# Microcontroller.net
KiCad netlist of a schematic drawn in Altium Designer
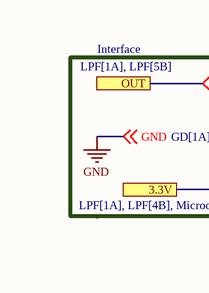
[diagram p0: Microcontroller.SchDoc, left]
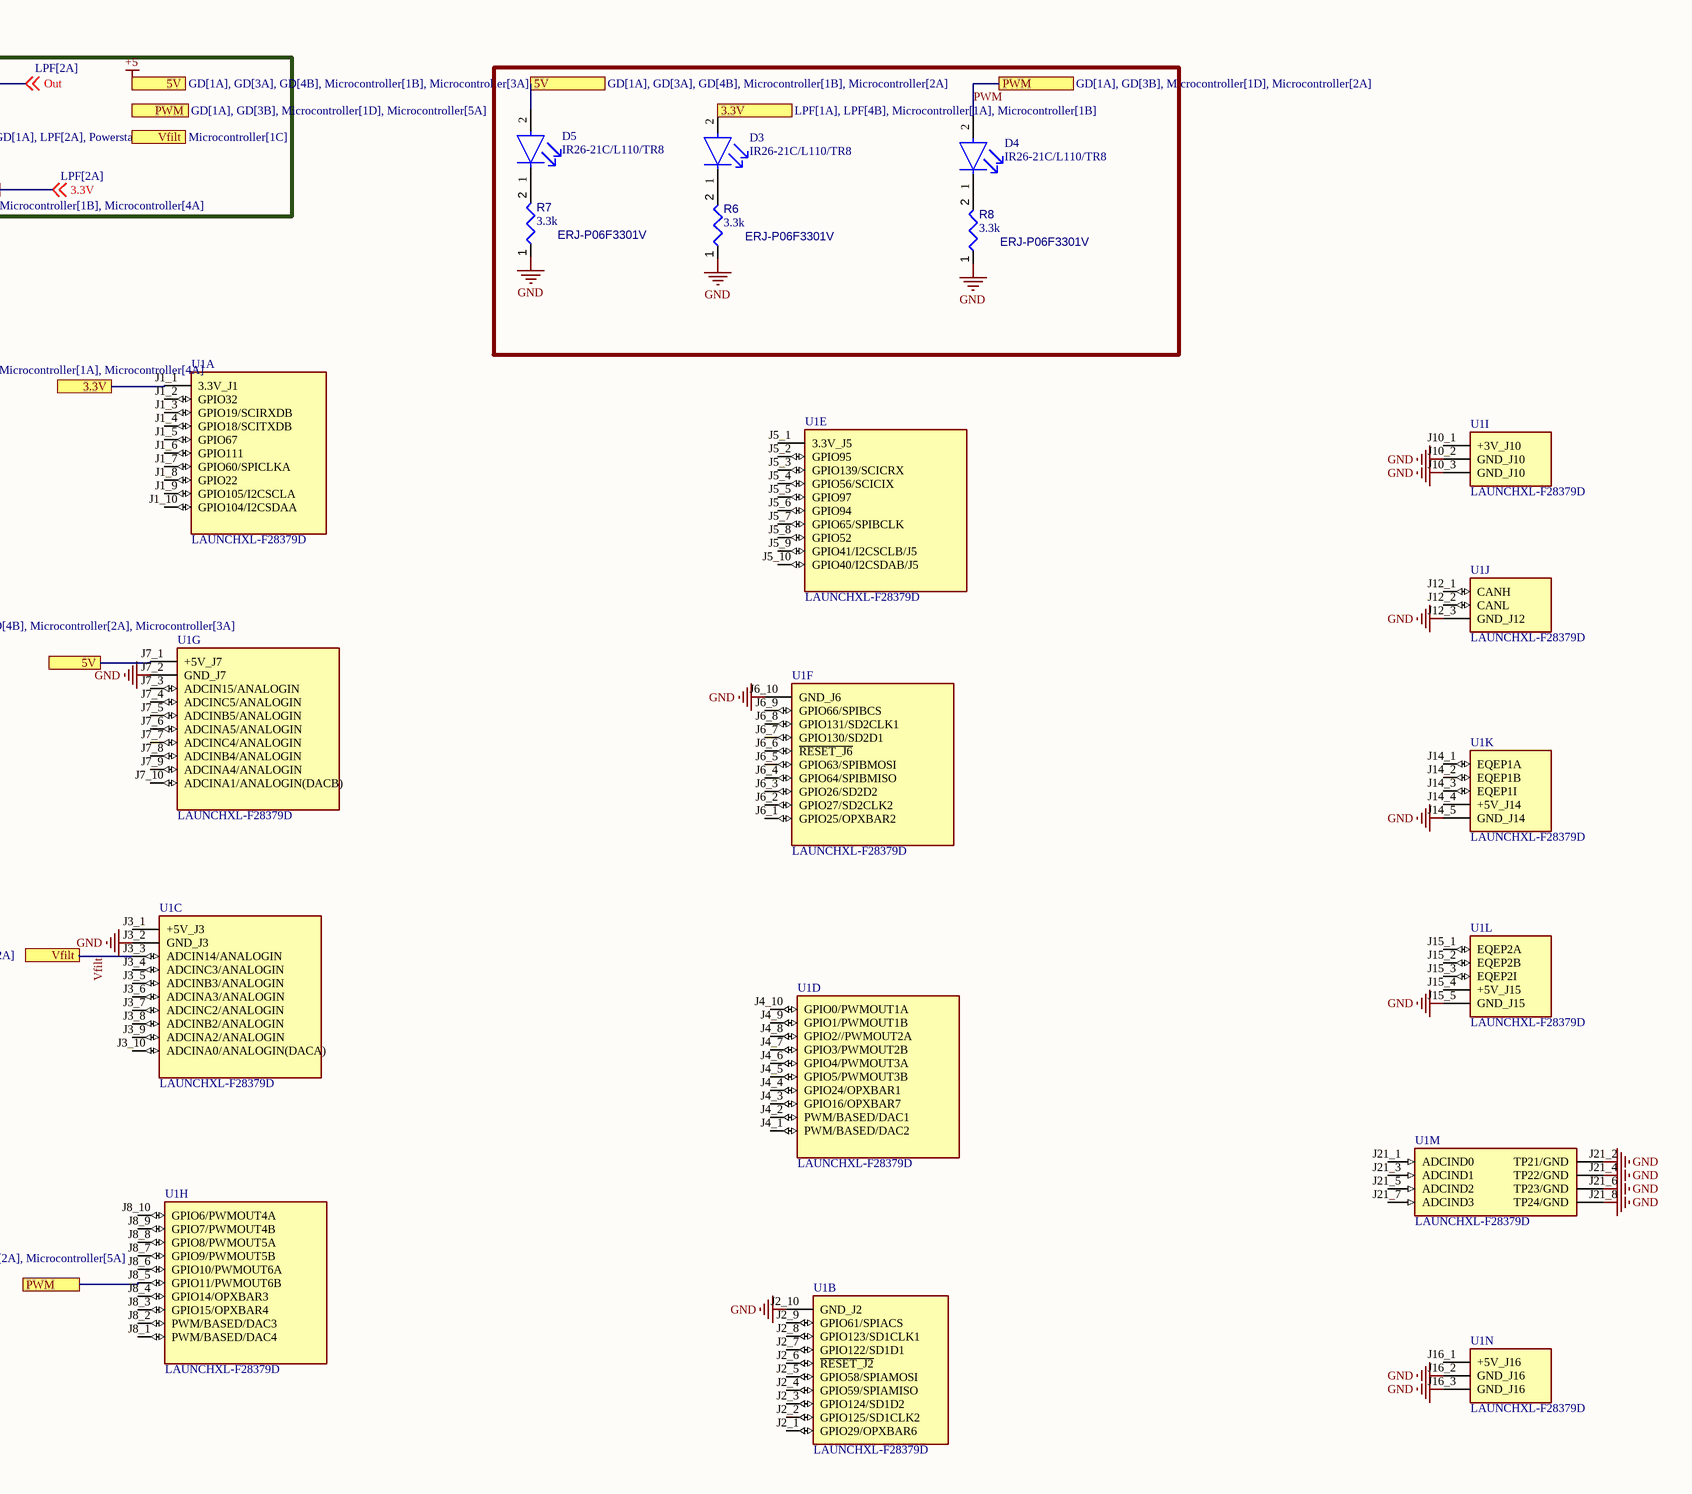
[diagram p1: Microcontroller.SchDoc, right]

(export (version "E")
  (design (tool "Eeschema 10.0.6"))
  (components
    (comp (ref "D3")
      (value "IR26-21C/L110/TR8")
      (footprint "FP-APTD3216CGCK-MFG")
      (description "LED GREEN CLEAR 2SMD")
      (libsource (lib "Altium Content Vault") (part "8706943c75ba83719d021d2fdc84c58"))
    )
    (comp (ref "D4")
      (value "IR26-21C/L110/TR8")
      (footprint "FP-APTD3216CGCK-MFG")
      (description "LED GREEN CLEAR 2SMD")
      (libsource (lib "Altium Content Vault") (part "8706943c75ba83719d021d2fdc84c58"))
    )
    (comp (ref "D5")
      (value "IR26-21C/L110/TR8")
      (footprint "FP-APTD3216CGCK-MFG")
      (description "LED GREEN CLEAR 2SMD")
      (libsource (lib "Altium Content Vault") (part "8706943c75ba83719d021d2fdc84c58"))
    )
    (comp (ref "R6")
      (value "ERJ-P06F3301V")
      (footprint "RESC0805(2012)_L")
      (description "1K 0.125W 5% 0805 (2012 Metric)  SMD")
      (fields
        (field (name "POWER") "125mW")
        (field (name "TOLERANCE") "5%")
        (field (name "ALTIUM_VALUE") "3.3k")
      )
      (libsource (lib "UWindsor Formula Electric") (part "1KR5J"))
    )
    (comp (ref "R7")
      (value "ERJ-P06F3301V")
      (footprint "RESC0805(2012)_L")
      (description "1K 0.125W 5% 0805 (2012 Metric)  SMD")
      (fields
        (field (name "POWER") "125mW")
        (field (name "TOLERANCE") "5%")
        (field (name "ALTIUM_VALUE") "3.3k")
      )
      (libsource (lib "UWindsor Formula Electric") (part "1KR5J"))
    )
    (comp (ref "R8")
      (value "ERJ-P06F3301V")
      (footprint "RESC0805(2012)_L")
      (description "1K 0.125W 5% 0805 (2012 Metric)  SMD")
      (fields
        (field (name "POWER") "125mW")
        (field (name "TOLERANCE") "5%")
        (field (name "ALTIUM_VALUE") "3.3k")
      )
      (libsource (lib "UWindsor Formula Electric") (part "1KR5J"))
    )
    (comp (ref "U1")
      (value "LAUNCHXL-F28379D")
      (footprint "MOD_LAUNCHXL-F28379D")
      (description "C2000 Delfino MCU F28379D LaunchPadâ„¢ development kit WITH 3D BODY")
      (fields (field (name "MF") "Texas Instruments"))
      (libsource (lib "UWindsor Formula Electric") (part "LAUNCHXL-F28379D"))
    )
  )
  (nets
    (net (code "1") (name "+5") (class "Default")
      (node (ref "D5") (pin "2") (pinfunction "A_2") (pintype "passive"))
      (node (ref "U1") (pin "J7_1") (pinfunction "+5V_J7_J7_1") (pintype "power_in"))
    )
    (net (code "2") (name "/PWM") (class "Default")
      (node (ref "D4") (pin "2") (pinfunction "A_2") (pintype "passive"))
      (node (ref "U1") (pin "J8_5") (pinfunction "GPIO11/PWMOUT6B_J8_5") (pintype "bidirectional"))
    )
    (net (code "3") (name "/Vfilt") (class "Default")
      (node (ref "U1") (pin "J3_3") (pinfunction "ADCIN14/ANALOGIN_J3_3") (pintype "bidirectional"))
    )
    (net (code "4") (name "3.3V") (class "Default")
      (node (ref "D3") (pin "2") (pinfunction "A_2") (pintype "passive"))
      (node (ref "U1") (pin "J1_1") (pinfunction "3.3V_J1_J1_1") (pintype "power_in"))
    )
    (net (code "5") (name "GND") (class "Default")
      (node (ref "R6") (pin "1") (pinfunction "1_1") (pintype "passive"))
      (node (ref "R7") (pin "1") (pinfunction "1_1") (pintype "passive"))
      (node (ref "R8") (pin "1") (pinfunction "1_1") (pintype "passive"))
      (node (ref "U1") (pin "J10_2") (pinfunction "GND_J10_J10_2") (pintype "power_in"))
      (node (ref "U1") (pin "J10_3") (pinfunction "GND_J10_J10_3") (pintype "power_in"))
      (node (ref "U1") (pin "J12_3") (pinfunction "GND_J12_J12_3") (pintype "power_in"))
      (node (ref "U1") (pin "J14_5") (pinfunction "GND_J14_J14_5") (pintype "power_in"))
      (node (ref "U1") (pin "J15_5") (pinfunction "GND_J15_J15_5") (pintype "power_in"))
      (node (ref "U1") (pin "J16_2") (pinfunction "GND_J16_J16_2") (pintype "power_in"))
      (node (ref "U1") (pin "J16_3") (pinfunction "GND_J16_J16_3") (pintype "power_in"))
      (node (ref "U1") (pin "J21_2") (pinfunction "TP21/GND_J21_2") (pintype "power_in"))
      (node (ref "U1") (pin "J21_4") (pinfunction "TP22/GND_J21_4") (pintype "power_in"))
      (node (ref "U1") (pin "J21_6") (pinfunction "TP23/GND_J21_6") (pintype "power_in"))
      (node (ref "U1") (pin "J21_8") (pinfunction "TP24/GND_J21_8") (pintype "power_in"))
      (node (ref "U1") (pin "J2_10") (pinfunction "GND_J2_J2_10") (pintype "power_in"))
      (node (ref "U1") (pin "J3_2") (pinfunction "GND_J3_J3_2") (pintype "power_in"))
      (node (ref "U1") (pin "J6_10") (pinfunction "GND_J6_J6_10") (pintype "power_in"))
      (node (ref "U1") (pin "J7_2") (pinfunction "GND_J7_J7_2") (pintype "power_in"))
    )
    (net (code "6") (name "Net-(D3-C)") (class "Default")
      (node (ref "D3") (pin "1") (pinfunction "C_1") (pintype "passive"))
      (node (ref "R6") (pin "2") (pinfunction "2_2") (pintype "passive"))
    )
    (net (code "7") (name "Net-(D4-C)") (class "Default")
      (node (ref "D4") (pin "1") (pinfunction "C_1") (pintype "passive"))
      (node (ref "R8") (pin "2") (pinfunction "2_2") (pintype "passive"))
    )
    (net (code "8") (name "Net-(D5-C)") (class "Default")
      (node (ref "D5") (pin "1") (pinfunction "C_1") (pintype "passive"))
      (node (ref "R7") (pin "2") (pinfunction "2_2") (pintype "passive"))
    )
    (net (code "10") (name "unconnected-(U1A-GPIO18{slash}SCITXDB-PadJ1_4)") (class "Default")
      (node (ref "U1") (pin "J1_4") (pinfunction "GPIO18/SCITXDB_J1_4") (pintype "bidirectional"))
    )
    (net (code "11") (name "unconnected-(U1A-GPIO19{slash}SCIRXDB-PadJ1_3)") (class "Default")
      (node (ref "U1") (pin "J1_3") (pinfunction "GPIO19/SCIRXDB_J1_3") (pintype "bidirectional"))
    )
    (net (code "12") (name "unconnected-(U1A-GPIO22-PadJ1_8)") (class "Default")
      (node (ref "U1") (pin "J1_8") (pinfunction "GPIO22_J1_8") (pintype "bidirectional"))
    )
    (net (code "13") (name "unconnected-(U1A-GPIO32-PadJ1_2)") (class "Default")
      (node (ref "U1") (pin "J1_2") (pinfunction "GPIO32_J1_2") (pintype "bidirectional"))
    )
    (net (code "14") (name "unconnected-(U1A-GPIO60{slash}SPICLKA-PadJ1_7)") (class "Default")
      (node (ref "U1") (pin "J1_7") (pinfunction "GPIO60/SPICLKA_J1_7") (pintype "bidirectional"))
    )
    (net (code "15") (name "unconnected-(U1A-GPIO67-PadJ1_5)") (class "Default")
      (node (ref "U1") (pin "J1_5") (pinfunction "GPIO67_J1_5") (pintype "bidirectional"))
    )
    (net (code "16") (name "unconnected-(U1A-GPIO104{slash}I2CSDAA-PadJ1_10)") (class "Default")
      (node (ref "U1") (pin "J1_10") (pinfunction "GPIO104/I2CSDAA_J1_10") (pintype "bidirectional"))
    )
    (net (code "17") (name "unconnected-(U1A-GPIO105{slash}I2CSCLA-PadJ1_9)") (class "Default")
      (node (ref "U1") (pin "J1_9") (pinfunction "GPIO105/I2CSCLA_J1_9") (pintype "bidirectional"))
    )
    (net (code "18") (name "unconnected-(U1A-GPIO111-PadJ1_6)") (class "Default")
      (node (ref "U1") (pin "J1_6") (pinfunction "GPIO111_J1_6") (pintype "bidirectional"))
    )
    (net (code "19") (name "unconnected-(U1B-GPIO29{slash}OPXBAR6-PadJ2_1)") (class "Default")
      (node (ref "U1") (pin "J2_1") (pinfunction "GPIO29/OPXBAR6_J2_1") (pintype "bidirectional"))
    )
    (net (code "20") (name "unconnected-(U1B-GPIO58{slash}SPIAMOSI-PadJ2_5)") (class "Default")
      (node (ref "U1") (pin "J2_5") (pinfunction "GPIO58/SPIAMOSI_J2_5") (pintype "bidirectional"))
    )
    (net (code "21") (name "unconnected-(U1B-GPIO59{slash}SPIAMISO-PadJ2_4)") (class "Default")
      (node (ref "U1") (pin "J2_4") (pinfunction "GPIO59/SPIAMISO_J2_4") (pintype "bidirectional"))
    )
    (net (code "22") (name "unconnected-(U1B-GPIO61{slash}SPIACS-PadJ2_9)") (class "Default")
      (node (ref "U1") (pin "J2_9") (pinfunction "GPIO61/SPIACS_J2_9") (pintype "bidirectional"))
    )
    (net (code "23") (name "unconnected-(U1B-GPIO122{slash}SD1D1-PadJ2_7)") (class "Default")
      (node (ref "U1") (pin "J2_7") (pinfunction "GPIO122/SD1D1_J2_7") (pintype "bidirectional"))
    )
    (net (code "24") (name "unconnected-(U1B-GPIO123{slash}SD1CLK1-PadJ2_8)") (class "Default")
      (node (ref "U1") (pin "J2_8") (pinfunction "GPIO123/SD1CLK1_J2_8") (pintype "bidirectional"))
    )
    (net (code "25") (name "unconnected-(U1B-GPIO124{slash}SD1D2-PadJ2_3)") (class "Default")
      (node (ref "U1") (pin "J2_3") (pinfunction "GPIO124/SD1D2_J2_3") (pintype "bidirectional"))
    )
    (net (code "26") (name "unconnected-(U1B-GPIO125{slash}SD1CLK2-PadJ2_2)") (class "Default")
      (node (ref "U1") (pin "J2_2") (pinfunction "GPIO125/SD1CLK2_J2_2") (pintype "bidirectional"))
    )
    (net (code "27") (name "unconnected-(U1B-~{RESET_J2}-PadJ2_6)") (class "Default")
      (node (ref "U1") (pin "J2_6") (pinfunction "~{RESET_J2}_J2_6") (pintype "bidirectional"))
    )
    (net (code "28") (name "unconnected-(U1C-+5V_J3-PadJ3_1)") (class "Default")
      (node (ref "U1") (pin "J3_1") (pinfunction "+5V_J3_J3_1") (pintype "power_in"))
    )
    (net (code "29") (name "unconnected-(U1C-ADCINA0{slash}ANALOGIN(DACA)-PadJ3_10)") (class "Default")
      (node (ref "U1") (pin "J3_10") (pinfunction "ADCINA0/ANALOGIN(DACA)_J3_10") (pintype "bidirectional"))
    )
    (net (code "30") (name "unconnected-(U1C-ADCINA2{slash}ANALOGIN-PadJ3_9)") (class "Default")
      (node (ref "U1") (pin "J3_9") (pinfunction "ADCINA2/ANALOGIN_J3_9") (pintype "bidirectional"))
    )
    (net (code "31") (name "unconnected-(U1C-ADCINA3{slash}ANALOGIN-PadJ3_6)") (class "Default")
      (node (ref "U1") (pin "J3_6") (pinfunction "ADCINA3/ANALOGIN_J3_6") (pintype "bidirectional"))
    )
    (net (code "32") (name "unconnected-(U1C-ADCINB2{slash}ANALOGIN-PadJ3_8)") (class "Default")
      (node (ref "U1") (pin "J3_8") (pinfunction "ADCINB2/ANALOGIN_J3_8") (pintype "bidirectional"))
    )
    (net (code "33") (name "unconnected-(U1C-ADCINB3{slash}ANALOGIN-PadJ3_5)") (class "Default")
      (node (ref "U1") (pin "J3_5") (pinfunction "ADCINB3/ANALOGIN_J3_5") (pintype "bidirectional"))
    )
    (net (code "34") (name "unconnected-(U1C-ADCINC2{slash}ANALOGIN-PadJ3_7)") (class "Default")
      (node (ref "U1") (pin "J3_7") (pinfunction "ADCINC2/ANALOGIN_J3_7") (pintype "bidirectional"))
    )
    (net (code "35") (name "unconnected-(U1C-ADCINC3{slash}ANALOGIN-PadJ3_4)") (class "Default")
      (node (ref "U1") (pin "J3_4") (pinfunction "ADCINC3/ANALOGIN_J3_4") (pintype "bidirectional"))
    )
    (net (code "36") (name "unconnected-(U1D-GPIO0{slash}PWMOUT1A-PadJ4_10)") (class "Default")
      (node (ref "U1") (pin "J4_10") (pinfunction "GPIO0/PWMOUT1A_J4_10") (pintype "bidirectional"))
    )
    (net (code "37") (name "unconnected-(U1D-GPIO1{slash}PWMOUT1B-PadJ4_9)") (class "Default")
      (node (ref "U1") (pin "J4_9") (pinfunction "GPIO1/PWMOUT1B_J4_9") (pintype "bidirectional"))
    )
    (net (code "38") (name "unconnected-(U1D-GPIO2{slash}{slash}PWMOUT2A-PadJ4_8)") (class "Default")
      (node (ref "U1") (pin "J4_8") (pinfunction "GPIO2//PWMOUT2A_J4_8") (pintype "bidirectional"))
    )
    (net (code "39") (name "unconnected-(U1D-GPIO3{slash}PWMOUT2B-PadJ4_7)") (class "Default")
      (node (ref "U1") (pin "J4_7") (pinfunction "GPIO3/PWMOUT2B_J4_7") (pintype "bidirectional"))
    )
    (net (code "40") (name "unconnected-(U1D-GPIO4{slash}PWMOUT3A-PadJ4_6)") (class "Default")
      (node (ref "U1") (pin "J4_6") (pinfunction "GPIO4/PWMOUT3A_J4_6") (pintype "bidirectional"))
    )
    (net (code "41") (name "unconnected-(U1D-GPIO5{slash}PWMOUT3B-PadJ4_5)") (class "Default")
      (node (ref "U1") (pin "J4_5") (pinfunction "GPIO5/PWMOUT3B_J4_5") (pintype "bidirectional"))
    )
    (net (code "42") (name "unconnected-(U1D-GPIO16{slash}OPXBAR7-PadJ4_3)") (class "Default")
      (node (ref "U1") (pin "J4_3") (pinfunction "GPIO16/OPXBAR7_J4_3") (pintype "bidirectional"))
    )
    (net (code "43") (name "unconnected-(U1D-GPIO24{slash}OPXBAR1-PadJ4_4)") (class "Default")
      (node (ref "U1") (pin "J4_4") (pinfunction "GPIO24/OPXBAR1_J4_4") (pintype "bidirectional"))
    )
    (net (code "44") (name "unconnected-(U1D-PWM{slash}BASED{slash}DAC1-PadJ4_2)") (class "Default")
      (node (ref "U1") (pin "J4_2") (pinfunction "PWM/BASED/DAC1_J4_2") (pintype "bidirectional"))
    )
    (net (code "45") (name "unconnected-(U1D-PWM{slash}BASED{slash}DAC2-PadJ4_1)") (class "Default")
      (node (ref "U1") (pin "J4_1") (pinfunction "PWM/BASED/DAC2_J4_1") (pintype "bidirectional"))
    )
    (net (code "46") (name "unconnected-(U1E-3.3V_J5-PadJ5_1)") (class "Default")
      (node (ref "U1") (pin "J5_1") (pinfunction "3.3V_J5_J5_1") (pintype "power_in"))
    )
    (net (code "47") (name "unconnected-(U1E-GPIO40{slash}I2CSDAB{slash}J5-PadJ5_10)") (class "Default")
      (node (ref "U1") (pin "J5_10") (pinfunction "GPIO40/I2CSDAB/J5_J5_10") (pintype "bidirectional"))
    )
    (net (code "48") (name "unconnected-(U1E-GPIO41{slash}I2CSCLB{slash}J5-PadJ5_9)") (class "Default")
      (node (ref "U1") (pin "J5_9") (pinfunction "GPIO41/I2CSCLB/J5_J5_9") (pintype "bidirectional"))
    )
    (net (code "49") (name "unconnected-(U1E-GPIO52-PadJ5_8)") (class "Default")
      (node (ref "U1") (pin "J5_8") (pinfunction "GPIO52_J5_8") (pintype "bidirectional"))
    )
    (net (code "50") (name "unconnected-(U1E-GPIO56{slash}SCICIX-PadJ5_4)") (class "Default")
      (node (ref "U1") (pin "J5_4") (pinfunction "GPIO56/SCICIX_J5_4") (pintype "bidirectional"))
    )
    (net (code "51") (name "unconnected-(U1E-GPIO65{slash}SPIBCLK-PadJ5_7)") (class "Default")
      (node (ref "U1") (pin "J5_7") (pinfunction "GPIO65/SPIBCLK_J5_7") (pintype "bidirectional"))
    )
    (net (code "52") (name "unconnected-(U1E-GPIO94-PadJ5_6)") (class "Default")
      (node (ref "U1") (pin "J5_6") (pinfunction "GPIO94_J5_6") (pintype "bidirectional"))
    )
    (net (code "53") (name "unconnected-(U1E-GPIO95-PadJ5_2)") (class "Default")
      (node (ref "U1") (pin "J5_2") (pinfunction "GPIO95_J5_2") (pintype "bidirectional"))
    )
    (net (code "54") (name "unconnected-(U1E-GPIO97-PadJ5_5)") (class "Default")
      (node (ref "U1") (pin "J5_5") (pinfunction "GPIO97_J5_5") (pintype "bidirectional"))
    )
    (net (code "55") (name "unconnected-(U1E-GPIO139{slash}SCICRX-PadJ5_3)") (class "Default")
      (node (ref "U1") (pin "J5_3") (pinfunction "GPIO139/SCICRX_J5_3") (pintype "bidirectional"))
    )
    (net (code "56") (name "unconnected-(U1F-GPIO25{slash}OPXBAR2-PadJ6_1)") (class "Default")
      (node (ref "U1") (pin "J6_1") (pinfunction "GPIO25/OPXBAR2_J6_1") (pintype "bidirectional"))
    )
    (net (code "57") (name "unconnected-(U1F-GPIO26{slash}SD2D2-PadJ6_3)") (class "Default")
      (node (ref "U1") (pin "J6_3") (pinfunction "GPIO26/SD2D2_J6_3") (pintype "bidirectional"))
    )
    (net (code "58") (name "unconnected-(U1F-GPIO27{slash}SD2CLK2-PadJ6_2)") (class "Default")
      (node (ref "U1") (pin "J6_2") (pinfunction "GPIO27/SD2CLK2_J6_2") (pintype "bidirectional"))
    )
    (net (code "59") (name "unconnected-(U1F-GPIO63{slash}SPIBMOSI-PadJ6_5)") (class "Default")
      (node (ref "U1") (pin "J6_5") (pinfunction "GPIO63/SPIBMOSI_J6_5") (pintype "bidirectional"))
    )
    (net (code "60") (name "unconnected-(U1F-GPIO64{slash}SPIBMISO-PadJ6_4)") (class "Default")
      (node (ref "U1") (pin "J6_4") (pinfunction "GPIO64/SPIBMISO_J6_4") (pintype "bidirectional"))
    )
    (net (code "61") (name "unconnected-(U1F-GPIO66{slash}SPIBCS-PadJ6_9)") (class "Default")
      (node (ref "U1") (pin "J6_9") (pinfunction "GPIO66/SPIBCS_J6_9") (pintype "bidirectional"))
    )
    (net (code "62") (name "unconnected-(U1F-GPIO130{slash}SD2D1-PadJ6_7)") (class "Default")
      (node (ref "U1") (pin "J6_7") (pinfunction "GPIO130/SD2D1_J6_7") (pintype "bidirectional"))
    )
    (net (code "63") (name "unconnected-(U1F-GPIO131{slash}SD2CLK1-PadJ6_8)") (class "Default")
      (node (ref "U1") (pin "J6_8") (pinfunction "GPIO131/SD2CLK1_J6_8") (pintype "bidirectional"))
    )
    (net (code "64") (name "unconnected-(U1F-~{RESET_J6}-PadJ6_6)") (class "Default")
      (node (ref "U1") (pin "J6_6") (pinfunction "~{RESET_J6}_J6_6") (pintype "bidirectional"))
    )
    (net (code "65") (name "unconnected-(U1G-ADCIN15{slash}ANALOGIN-PadJ7_3)") (class "Default")
      (node (ref "U1") (pin "J7_3") (pinfunction "ADCIN15/ANALOGIN_J7_3") (pintype "bidirectional"))
    )
    (net (code "66") (name "unconnected-(U1G-ADCINA1{slash}ANALOGIN(DACB)-PadJ7_10)") (class "Default")
      (node (ref "U1") (pin "J7_10") (pinfunction "ADCINA1/ANALOGIN(DACB)_J7_10") (pintype "bidirectional"))
    )
    (net (code "67") (name "unconnected-(U1G-ADCINA4{slash}ANALOGIN-PadJ7_9)") (class "Default")
      (node (ref "U1") (pin "J7_9") (pinfunction "ADCINA4/ANALOGIN_J7_9") (pintype "bidirectional"))
    )
    (net (code "68") (name "unconnected-(U1G-ADCINA5{slash}ANALOGIN-PadJ7_6)") (class "Default")
      (node (ref "U1") (pin "J7_6") (pinfunction "ADCINA5/ANALOGIN_J7_6") (pintype "bidirectional"))
    )
    (net (code "69") (name "unconnected-(U1G-ADCINB4{slash}ANALOGIN-PadJ7_8)") (class "Default")
      (node (ref "U1") (pin "J7_8") (pinfunction "ADCINB4/ANALOGIN_J7_8") (pintype "bidirectional"))
    )
    (net (code "70") (name "unconnected-(U1G-ADCINB5{slash}ANALOGIN-PadJ7_5)") (class "Default")
      (node (ref "U1") (pin "J7_5") (pinfunction "ADCINB5/ANALOGIN_J7_5") (pintype "bidirectional"))
    )
    (net (code "71") (name "unconnected-(U1G-ADCINC4{slash}ANALOGIN-PadJ7_7)") (class "Default")
      (node (ref "U1") (pin "J7_7") (pinfunction "ADCINC4/ANALOGIN_J7_7") (pintype "bidirectional"))
    )
    (net (code "72") (name "unconnected-(U1G-ADCINC5{slash}ANALOGIN-PadJ7_4)") (class "Default")
      (node (ref "U1") (pin "J7_4") (pinfunction "ADCINC5/ANALOGIN_J7_4") (pintype "bidirectional"))
    )
    (net (code "73") (name "unconnected-(U1H-GPIO6{slash}PWMOUT4A-PadJ8_10)") (class "Default")
      (node (ref "U1") (pin "J8_10") (pinfunction "GPIO6/PWMOUT4A_J8_10") (pintype "bidirectional"))
    )
    (net (code "74") (name "unconnected-(U1H-GPIO7{slash}PWMOUT4B-PadJ8_9)") (class "Default")
      (node (ref "U1") (pin "J8_9") (pinfunction "GPIO7/PWMOUT4B_J8_9") (pintype "bidirectional"))
    )
    (net (code "75") (name "unconnected-(U1H-GPIO8{slash}PWMOUT5A-PadJ8_8)") (class "Default")
      (node (ref "U1") (pin "J8_8") (pinfunction "GPIO8/PWMOUT5A_J8_8") (pintype "bidirectional"))
    )
    (net (code "76") (name "unconnected-(U1H-GPIO9{slash}PWMOUT5B-PadJ8_7)") (class "Default")
      (node (ref "U1") (pin "J8_7") (pinfunction "GPIO9/PWMOUT5B_J8_7") (pintype "bidirectional"))
    )
    (net (code "77") (name "unconnected-(U1H-GPIO10{slash}PWMOUT6A-PadJ8_6)") (class "Default")
      (node (ref "U1") (pin "J8_6") (pinfunction "GPIO10/PWMOUT6A_J8_6") (pintype "bidirectional"))
    )
    (net (code "78") (name "unconnected-(U1H-GPIO14{slash}OPXBAR3-PadJ8_4)") (class "Default")
      (node (ref "U1") (pin "J8_4") (pinfunction "GPIO14/OPXBAR3_J8_4") (pintype "bidirectional"))
    )
    (net (code "79") (name "unconnected-(U1H-GPIO15{slash}OPXBAR4-PadJ8_3)") (class "Default")
      (node (ref "U1") (pin "J8_3") (pinfunction "GPIO15/OPXBAR4_J8_3") (pintype "bidirectional"))
    )
    (net (code "80") (name "unconnected-(U1H-PWM{slash}BASED{slash}DAC3-PadJ8_2)") (class "Default")
      (node (ref "U1") (pin "J8_2") (pinfunction "PWM/BASED/DAC3_J8_2") (pintype "bidirectional"))
    )
    (net (code "81") (name "unconnected-(U1H-PWM{slash}BASED{slash}DAC4-PadJ8_1)") (class "Default")
      (node (ref "U1") (pin "J8_1") (pinfunction "PWM/BASED/DAC4_J8_1") (pintype "bidirectional"))
    )
    (net (code "82") (name "unconnected-(U1I-+3V_J10-PadJ10_1)") (class "Default")
      (node (ref "U1") (pin "J10_1") (pinfunction "+3V_J10_J10_1") (pintype "power_in"))
    )
    (net (code "83") (name "unconnected-(U1J-CANH-PadJ12_1)") (class "Default")
      (node (ref "U1") (pin "J12_1") (pinfunction "CANH_J12_1") (pintype "bidirectional"))
    )
    (net (code "84") (name "unconnected-(U1J-CANL-PadJ12_2)") (class "Default")
      (node (ref "U1") (pin "J12_2") (pinfunction "CANL_J12_2") (pintype "bidirectional"))
    )
    (net (code "85") (name "unconnected-(U1K-+5V_J14-PadJ14_4)") (class "Default")
      (node (ref "U1") (pin "J14_4") (pinfunction "+5V_J14_J14_4") (pintype "power_in"))
    )
    (net (code "86") (name "unconnected-(U1K-EQEP1A-PadJ14_1)") (class "Default")
      (node (ref "U1") (pin "J14_1") (pinfunction "EQEP1A_J14_1") (pintype "bidirectional"))
    )
    (net (code "87") (name "unconnected-(U1K-EQEP1B-PadJ14_2)") (class "Default")
      (node (ref "U1") (pin "J14_2") (pinfunction "EQEP1B_J14_2") (pintype "bidirectional"))
    )
    (net (code "88") (name "unconnected-(U1K-EQEP1I-PadJ14_3)") (class "Default")
      (node (ref "U1") (pin "J14_3") (pinfunction "EQEP1I_J14_3") (pintype "bidirectional"))
    )
    (net (code "89") (name "unconnected-(U1L-+5V_J15-PadJ15_4)") (class "Default")
      (node (ref "U1") (pin "J15_4") (pinfunction "+5V_J15_J15_4") (pintype "power_in"))
    )
    (net (code "90") (name "unconnected-(U1L-EQEP2A-PadJ15_1)") (class "Default")
      (node (ref "U1") (pin "J15_1") (pinfunction "EQEP2A_J15_1") (pintype "bidirectional"))
    )
    (net (code "91") (name "unconnected-(U1L-EQEP2B-PadJ15_2)") (class "Default")
      (node (ref "U1") (pin "J15_2") (pinfunction "EQEP2B_J15_2") (pintype "bidirectional"))
    )
    (net (code "92") (name "unconnected-(U1L-EQEP2I-PadJ15_3)") (class "Default")
      (node (ref "U1") (pin "J15_3") (pinfunction "EQEP2I_J15_3") (pintype "bidirectional"))
    )
    (net (code "93") (name "unconnected-(U1M-ADCIND0-PadJ21_1)") (class "Default")
      (node (ref "U1") (pin "J21_1") (pinfunction "ADCIND0_J21_1") (pintype "input"))
    )
    (net (code "94") (name "unconnected-(U1M-ADCIND1-PadJ21_3)") (class "Default")
      (node (ref "U1") (pin "J21_3") (pinfunction "ADCIND1_J21_3") (pintype "input"))
    )
    (net (code "95") (name "unconnected-(U1M-ADCIND2-PadJ21_5)") (class "Default")
      (node (ref "U1") (pin "J21_5") (pinfunction "ADCIND2_J21_5") (pintype "input"))
    )
    (net (code "96") (name "unconnected-(U1M-ADCIND3-PadJ21_7)") (class "Default")
      (node (ref "U1") (pin "J21_7") (pinfunction "ADCIND3_J21_7") (pintype "input"))
    )
    (net (code "97") (name "unconnected-(U1N-+5V_J16-PadJ16_1)") (class "Default")
      (node (ref "U1") (pin "J16_1") (pinfunction "+5V_J16_J16_1") (pintype "power_in"))
    )
  )
)
